# Zirkulation.net
KiCad netlist of a schematic drawn in EAGLE
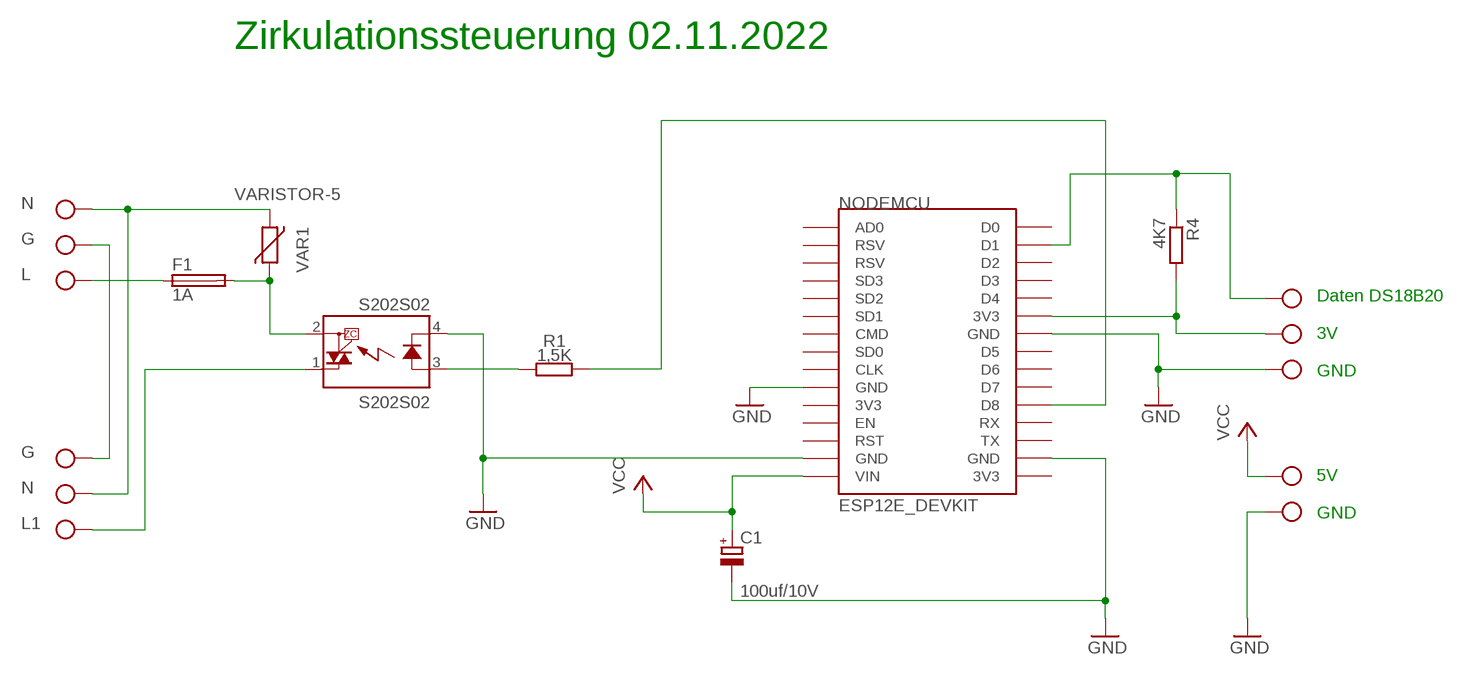
[diagram p0: schematic, sheet 1]

(export (version "E")
  (design (tool "Eeschema 10.0.6"))
  (components
    (comp (ref "C1")
      (value "100uf/10V")
      (footprint "eagle-import:E2,5-7")
      (libsource (lib "eagle-import") (part "CPOL-EUE2.5-7"))
    )
    (comp (ref "F1")
      (value "1A")
      (footprint "eagle-import:SH22,5")
      (libsource (lib "eagle-import") (part "FUSESH22,5"))
    )
    (comp (ref "IN")
      (value "MKDSN1,5/3-5,08")
      (footprint "eagle-import:MKDSN1,5_3-5,08")
      (libsource (lib "eagle-import") (part "MKDSN1,5/3-5,08"))
    )
    (comp (ref "NODEMCU")
      (value "ESP12E_DEVKIT")
      (footprint "eagle-import:ESP12E_DEVKIT")
      (libsource (lib "eagle-import") (part "ESP12E_DEVKIT"))
    )
    (comp (ref "OUT")
      (value "MKDSN1,5/3-5,08")
      (footprint "eagle-import:MKDSN1,5_3-5,08")
      (libsource (lib "eagle-import") (part "MKDSN1,5/3-5,08"))
    )
    (comp (ref "PWR")
      (value "MKDSN1,5/2-5,08")
      (footprint "eagle-import:MKDSN1,5_2-5,08")
      (libsource (lib "eagle-import") (part "MKDSN1,5/2-5,08"))
    )
    (comp (ref "R1")
      (value "1,5K")
      (footprint "eagle-import:0204_5")
      (libsource (lib "eagle-import") (part "R-EU_0204/5"))
    )
    (comp (ref "R4")
      (value "4K7")
      (footprint "eagle-import:0204_5")
      (libsource (lib "eagle-import") (part "R-EU_0204/5"))
    )
    (comp (ref "S202S02")
      (value "S202S02")
      (footprint "eagle-import:S202S02")
      (fields (field (name "MPN") "S202S02F"))
      (libsource (lib "eagle-import") (part "S02S022"))
    )
    (comp (ref "SENSOR")
      (value "MKDSN1,5/3-5,08")
      (footprint "eagle-import:MKDSN1,5_3-5,08")
      (libsource (lib "eagle-import") (part "MKDSN1,5/3-5,08"))
    )
    (comp (ref "VAR1")
      (value "VARISTOR-5")
      (footprint "eagle-import:R-5")
      (libsource (lib "eagle-import") (part "VARISTOR-5"))
    )
  )
  (nets
    (net (code "1") (name "/G") (class "Default")
      (node (ref "IN") (pin "3") (pinfunction "KL_3") (pintype "passive"))
      (node (ref "OUT") (pin "3") (pinfunction "KL_3") (pintype "passive"))
    )
    (net (code "2") (name "/L") (class "Default")
      (node (ref "F1") (pin "1") (pinfunction "1_1") (pintype "passive"))
      (node (ref "IN") (pin "1") (pinfunction "KL_1") (pintype "passive"))
    )
    (net (code "3") (name "/L1") (class "Default")
      (node (ref "OUT") (pin "1") (pinfunction "KL_1") (pintype "passive"))
      (node (ref "S202S02") (pin "1") (pinfunction "DS1_1") (pintype "passive"))
    )
    (net (code "4") (name "/N") (class "Default")
      (node (ref "IN") (pin "2") (pinfunction "KL_2") (pintype "passive"))
      (node (ref "OUT") (pin "2") (pinfunction "KL_2") (pintype "passive"))
      (node (ref "VAR1") (pin "2") (pinfunction "2_2") (pintype "passive"))
    )
    (net (code "5") (name "GND") (class "Default")
      (node (ref "C1") (pin "-") (pinfunction "-_-") (pintype "passive"))
      (node (ref "NODEMCU") (pin "GND@0") (pinfunction "GND_GND@0") (pintype "bidirectional"))
      (node (ref "NODEMCU") (pin "GND@1") (pinfunction "GND_GND@1") (pintype "bidirectional"))
      (node (ref "NODEMCU") (pin "GND@2") (pinfunction "GND_GND@2") (pintype "bidirectional"))
      (node (ref "NODEMCU") (pin "GND@3") (pinfunction "GND_GND@3") (pintype "bidirectional"))
      (node (ref "PWR") (pin "2") (pinfunction "KL_2") (pintype "passive"))
      (node (ref "S202S02") (pin "4") (pinfunction "K_4") (pintype "passive"))
      (node (ref "SENSOR") (pin "3") (pinfunction "KL_3") (pintype "passive"))
    )
    (net (code "6") (name "Net-(NODEMCU-PadD8)") (class "Default")
      (node (ref "NODEMCU") (pin "D8") (pinfunction "D8_D8") (pintype "bidirectional"))
      (node (ref "R1") (pin "1") (pinfunction "1_1") (pintype "passive"))
    )
    (net (code "7") (name "Net-(S202S02-A)") (class "Default")
      (node (ref "R1") (pin "2") (pinfunction "2_2") (pintype "passive"))
      (node (ref "S202S02") (pin "3") (pinfunction "A_3") (pintype "passive"))
    )
    (net (code "8") (name "Net-(S202S02-DS2)") (class "Default")
      (node (ref "F1") (pin "2") (pinfunction "2_2") (pintype "passive"))
      (node (ref "S202S02") (pin "2") (pinfunction "DS2_2") (pintype "passive"))
      (node (ref "VAR1") (pin "1") (pinfunction "1_1") (pintype "passive"))
    )
    (net (code "9") (name "Net-(SENSORA-KL)") (class "Default")
      (node (ref "NODEMCU") (pin "D1") (pinfunction "D1_D1") (pintype "bidirectional"))
      (node (ref "R4") (pin "1") (pinfunction "1_1") (pintype "passive"))
      (node (ref "SENSOR") (pin "1") (pinfunction "KL_1") (pintype "passive"))
    )
    (net (code "10") (name "Net-(SENSORB-KL)") (class "Default")
      (node (ref "NODEMCU") (pin "3V3@1") (pinfunction "3V3_3V3@1") (pintype "bidirectional"))
      (node (ref "R4") (pin "2") (pinfunction "2_2") (pintype "passive"))
      (node (ref "SENSOR") (pin "2") (pinfunction "KL_2") (pintype "passive"))
    )
    (net (code "11") (name "VCC") (class "Default")
      (node (ref "C1") (pin "+") (pinfunction "+_+") (pintype "passive"))
      (node (ref "NODEMCU") (pin "VIN") (pinfunction "VIN_VIN") (pintype "bidirectional"))
      (node (ref "PWR") (pin "1") (pinfunction "KL_1") (pintype "passive"))
    )
    (net (code "12") (name "unconnected-(NODEMCU-3V3-Pad3V3@0)") (class "Default")
      (node (ref "NODEMCU") (pin "3V3@0") (pinfunction "3V3_3V3@0") (pintype "bidirectional"))
    )
    (net (code "13") (name "unconnected-(NODEMCU-3V3-Pad3V3@2)") (class "Default")
      (node (ref "NODEMCU") (pin "3V3@2") (pinfunction "3V3_3V3@2") (pintype "bidirectional"))
    )
    (net (code "14") (name "unconnected-(NODEMCU-PadAD0)") (class "Default")
      (node (ref "NODEMCU") (pin "AD0") (pinfunction "AD0_AD0") (pintype "bidirectional"))
    )
    (net (code "15") (name "unconnected-(NODEMCU-PadCLK)") (class "Default")
      (node (ref "NODEMCU") (pin "CLK") (pinfunction "CLK_CLK") (pintype "bidirectional"))
    )
    (net (code "16") (name "unconnected-(NODEMCU-PadCMD)") (class "Default")
      (node (ref "NODEMCU") (pin "CMD") (pinfunction "CMD_CMD") (pintype "bidirectional"))
    )
    (net (code "17") (name "unconnected-(NODEMCU-PadD0)") (class "Default")
      (node (ref "NODEMCU") (pin "D0") (pinfunction "D0_D0") (pintype "bidirectional"))
    )
    (net (code "18") (name "unconnected-(NODEMCU-PadD2)") (class "Default")
      (node (ref "NODEMCU") (pin "D2") (pinfunction "D2_D2") (pintype "bidirectional"))
    )
    (net (code "19") (name "unconnected-(NODEMCU-PadD3)") (class "Default")
      (node (ref "NODEMCU") (pin "D3") (pinfunction "D3_D3") (pintype "bidirectional"))
    )
    (net (code "20") (name "unconnected-(NODEMCU-PadD4)") (class "Default")
      (node (ref "NODEMCU") (pin "D4") (pinfunction "D4_D4") (pintype "bidirectional"))
    )
    (net (code "21") (name "unconnected-(NODEMCU-PadD5)") (class "Default")
      (node (ref "NODEMCU") (pin "D5") (pinfunction "D5_D5") (pintype "bidirectional"))
    )
    (net (code "22") (name "unconnected-(NODEMCU-PadD6)") (class "Default")
      (node (ref "NODEMCU") (pin "D6") (pinfunction "D6_D6") (pintype "bidirectional"))
    )
    (net (code "23") (name "unconnected-(NODEMCU-PadD7)") (class "Default")
      (node (ref "NODEMCU") (pin "D7") (pinfunction "D7_D7") (pintype "bidirectional"))
    )
    (net (code "24") (name "unconnected-(NODEMCU-PadEN)") (class "Default")
      (node (ref "NODEMCU") (pin "EN") (pinfunction "EN_EN") (pintype "bidirectional"))
    )
    (net (code "25") (name "unconnected-(NODEMCU-PadRST)") (class "Default")
      (node (ref "NODEMCU") (pin "RST") (pinfunction "RST_RST") (pintype "bidirectional"))
    )
    (net (code "26") (name "unconnected-(NODEMCU-PadRX)") (class "Default")
      (node (ref "NODEMCU") (pin "RX") (pinfunction "RX_RX") (pintype "bidirectional"))
    )
    (net (code "27") (name "unconnected-(NODEMCU-PadSD0)") (class "Default")
      (node (ref "NODEMCU") (pin "SD0") (pinfunction "SD0_SD0") (pintype "bidirectional"))
    )
    (net (code "28") (name "unconnected-(NODEMCU-PadSD1)") (class "Default")
      (node (ref "NODEMCU") (pin "SD1") (pinfunction "SD1_SD1") (pintype "bidirectional"))
    )
    (net (code "29") (name "unconnected-(NODEMCU-PadSD2)") (class "Default")
      (node (ref "NODEMCU") (pin "SD2") (pinfunction "SD2_SD2") (pintype "bidirectional"))
    )
    (net (code "30") (name "unconnected-(NODEMCU-PadSD3)") (class "Default")
      (node (ref "NODEMCU") (pin "SD3") (pinfunction "SD3_SD3") (pintype "bidirectional"))
    )
    (net (code "31") (name "unconnected-(NODEMCU-PadTX)") (class "Default")
      (node (ref "NODEMCU") (pin "TX") (pinfunction "TX_TX") (pintype "bidirectional"))
    )
    (net (code "32") (name "unconnected-(NODEMCU-RSV-PadRSV@0)") (class "Default")
      (node (ref "NODEMCU") (pin "RSV@0") (pinfunction "RSV_RSV@0") (pintype "bidirectional"))
    )
    (net (code "33") (name "unconnected-(NODEMCU-RSV-PadRSV@1)") (class "Default")
      (node (ref "NODEMCU") (pin "RSV@1") (pinfunction "RSV_RSV@1") (pintype "bidirectional"))
    )
  )
)
